# power.net
KiCad netlist of a schematic drawn in Altium Designer
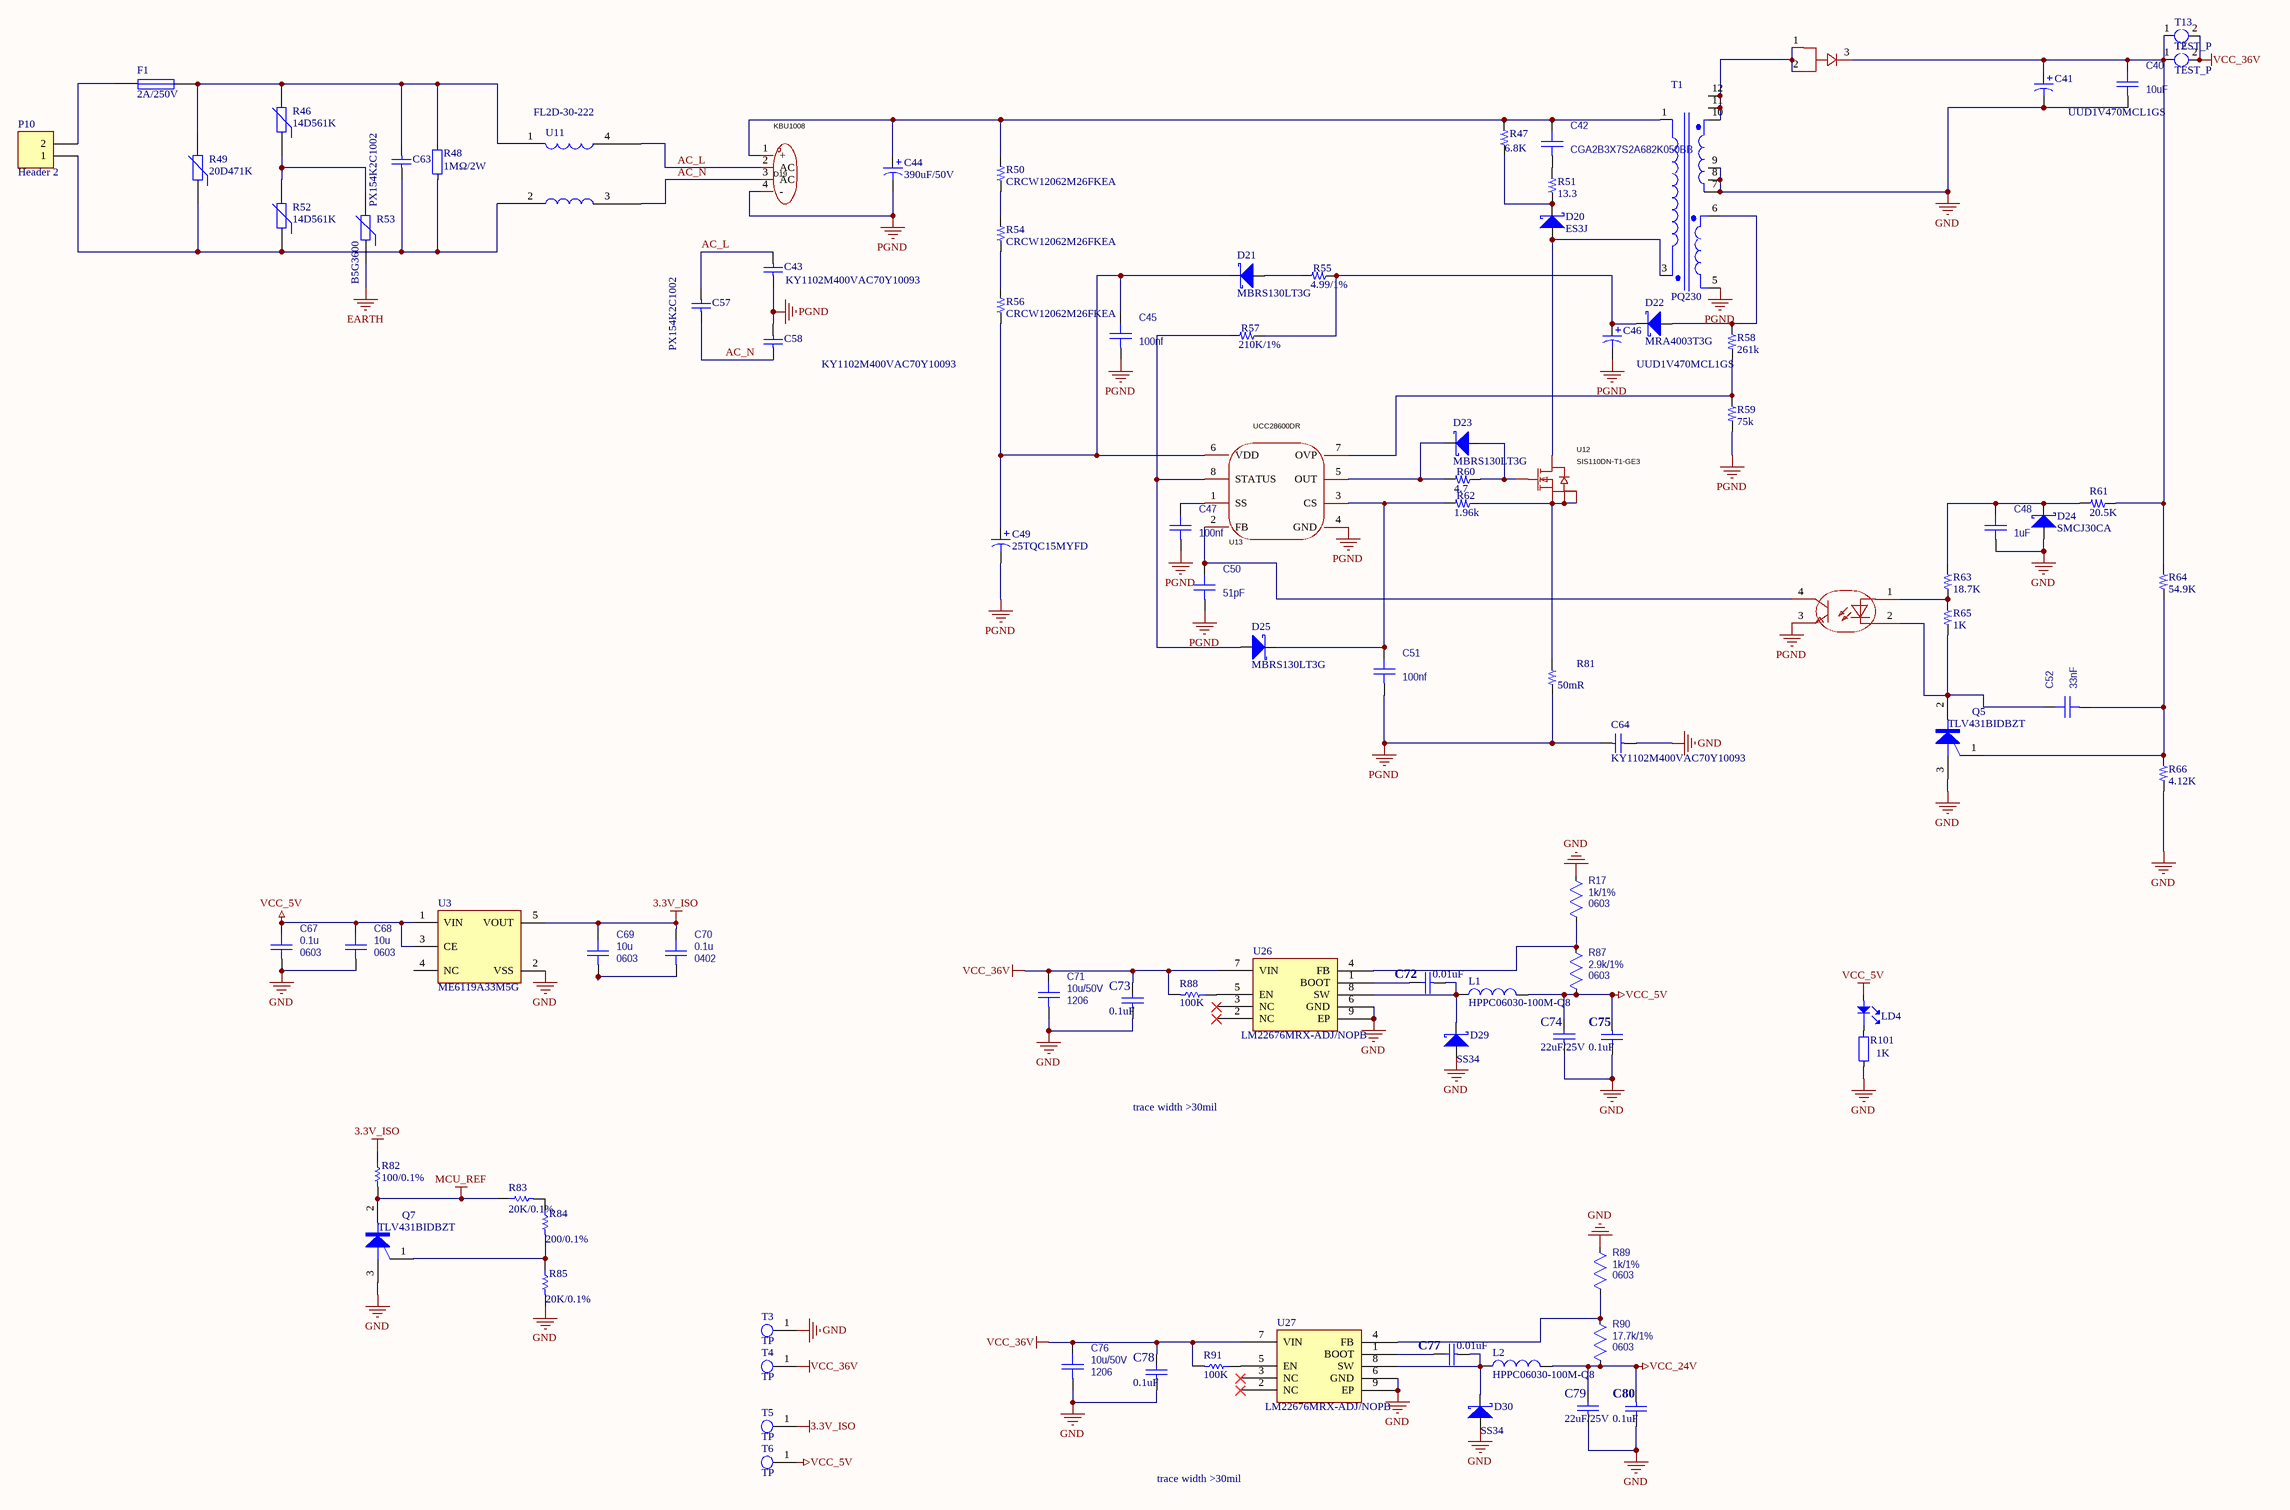
[diagram p0: power.SchDoc]

(export (version "E")
  (design (tool "Eeschema 10.0.6"))
  (components
    (comp (ref "C40")
      (value "Capacitor_0603")
      (footprint "0603c")
      (description "Capacitor, MLCC")
      (fields
        (field (name "MANUFACTURER") "Murata Electronics")
        (field (name "PARTNUMBER") "GRM188R61A106KE69D")
        (field (name "PACKAGE") "10uF")
      )
      (libsource (lib "Karl") (part "Capacitor_0603"))
    )
    (comp (ref "C41")
      (value "UUD1V470MCL1GS")
      (footprint "Φ10×10")
      (description "Polarized Capacitor (Radial)")
      (fields (field (name "PUBLISHER") "Altium Limited"))
      (libsource (lib "Miscellaneous Devices") (part "Cap Pol1"))
    )
    (comp (ref "C42")
      (value "Capacitor_0603")
      (footprint "0402c")
      (description "Capacitor, MLCC")
      (fields
        (field (name "MANUFACTURER") "Murata Electronics")
        (field (name "PARTNUMBER") "GRM188R61A106KE69D")
        (field (name "PACKAGE") "CGA2B3X7S2A682K050BB")
      )
      (libsource (lib "Karl") (part "Capacitor_0603"))
    )
    (comp (ref "C43")
      (value "KY1102M400VAC70Y10093")
      (footprint "CAP-TH_L7.5-W4.5-P10.00-D0.6")
      (description "Capacitor")
      (fields (field (name "PUBLISHER") "Altium Limited"))
      (libsource (lib "Miscellaneous Devices") (part "Cap"))
    )
    (comp (ref "C44")
      (value "390uF/50V")
      (footprint "LGX2H391MELC50")
      (description "Polarized Capacitor (Radial)")
      (fields (field (name "PUBLISHER") "Altium Limited"))
      (libsource (lib "Miscellaneous Devices") (part "Cap Pol1"))
    )
    (comp (ref "C45")
      (value "Capacitor_0603")
      (footprint "0603c")
      (description "Capacitor, MLCC")
      (fields
        (field (name "MANUFACTURER") "Murata Electronics")
        (field (name "PARTNUMBER") "GRM188R61A106KE69D")
        (field (name "PACKAGE") "100nf")
      )
      (libsource (lib "Karl") (part "Capacitor_0603"))
    )
    (comp (ref "C46")
      (value "UUD1V470MCL1GS")
      (footprint "Φ10×10")
      (description "Polarized Capacitor (Radial)")
      (fields (field (name "PUBLISHER") "Altium Limited"))
      (libsource (lib "Miscellaneous Devices") (part "Cap Pol1"))
    )
    (comp (ref "C47")
      (value "Capacitor_0603")
      (footprint "0603c")
      (description "Capacitor, MLCC")
      (fields
        (field (name "MANUFACTURER") "Murata Electronics")
        (field (name "PARTNUMBER") "GRM188R61A106KE69D")
        (field (name "PACKAGE") "100nf")
      )
      (libsource (lib "Karl") (part "Capacitor_0603"))
    )
    (comp (ref "C48")
      (value "Capacitor_0603")
      (footprint "0402c")
      (description "Capacitor, MLCC")
      (fields
        (field (name "MANUFACTURER") "Murata Electronics")
        (field (name "PARTNUMBER") "GRM188R61A106KE69D")
        (field (name "PACKAGE") "1uF")
      )
      (libsource (lib "Karl") (part "Capacitor_0603"))
    )
    (comp (ref "C49")
      (value "25TQC15MYFD")
      (footprint "7343")
      (description "Polarized Capacitor (Radial)")
      (fields (field (name "PUBLISHER") "Altium Limited"))
      (libsource (lib "Miscellaneous Devices") (part "Cap Pol1"))
    )
    (comp (ref "C50")
      (value "Capacitor_0603")
      (footprint "0603c")
      (description "Capacitor, MLCC")
      (fields
        (field (name "MANUFACTURER") "Murata Electronics")
        (field (name "PARTNUMBER") "GRM188R61A106KE69D")
        (field (name "PACKAGE") "51pF")
      )
      (libsource (lib "Karl") (part "Capacitor_0603"))
    )
    (comp (ref "C51")
      (value "Capacitor_0603")
      (footprint "0603c")
      (description "Capacitor, MLCC")
      (fields
        (field (name "MANUFACTURER") "Murata Electronics")
        (field (name "PARTNUMBER") "GRM188R61A106KE69D")
        (field (name "PACKAGE") "100nf")
      )
      (libsource (lib "Karl") (part "Capacitor_0603"))
    )
    (comp (ref "C52")
      (value "Capacitor_0603")
      (footprint "0603c")
      (description "Capacitor, MLCC")
      (fields
        (field (name "MANUFACTURER") "Murata Electronics")
        (field (name "PARTNUMBER") "GRM188R61A106KE69D")
        (field (name "PACKAGE") "33nF")
      )
      (libsource (lib "Karl") (part "Capacitor_0603"))
    )
    (comp (ref "C57")
      (value "PX154K2C1002")
      (footprint "CAP-TH_L13.0-W6.0-P10.00-D0.6")
      (description "Capacitor")
      (fields (field (name "PUBLISHER") "Altium Limited"))
      (libsource (lib "Miscellaneous Devices") (part "Cap"))
    )
    (comp (ref "C58")
      (value "KY1102M400VAC70Y10093")
      (footprint "CAP-TH_L7.5-W4.5-P10.00-D0.6")
      (description "Capacitor")
      (fields (field (name "PUBLISHER") "Altium Limited"))
      (libsource (lib "Miscellaneous Devices") (part "Cap"))
    )
    (comp (ref "C63")
      (value "PX154K2C1002")
      (footprint "CAP-TH_L13.0-W6.0-P10.00-D0.6")
      (description "Capacitor")
      (fields (field (name "PUBLISHER") "Altium Limited"))
      (libsource (lib "Miscellaneous Devices") (part "Cap"))
    )
    (comp (ref "C64")
      (value "KY1102M400VAC70Y10093")
      (footprint "CAP-TH_L7.5-W4.5-P10.00-D0.6")
      (description "Capacitor")
      (fields (field (name "PUBLISHER") "Altium Limited"))
      (libsource (lib "Miscellaneous Devices") (part "Cap"))
    )
    (comp (ref "C67")
      (value "0.1u")
      (footprint "CAPC1608X092N_0603")
      (description "Capacitor, MLCC")
      (fields
        (field (name "MANUFACTURER") "KEMET")
        (field (name "PARTNUMBER") "C0603C104M5RACTU")
        (field (name "PACKAGE") "0603")
      )
      (libsource (lib "Karl") (part "Capacitor_0603"))
    )
    (comp (ref "C68")
      (value "10u")
      (footprint "CAPC1608X092N_0603")
      (description "Capacitor, MLCC")
      (fields
        (field (name "MANUFACTURER") "Murata Electronics")
        (field (name "PARTNUMBER") "GRM188R61A106KE69D")
        (field (name "PACKAGE") "0603")
      )
      (libsource (lib "Karl") (part "Capacitor_0603"))
    )
    (comp (ref "C69")
      (value "10u")
      (footprint "CAPC1608X092N_0603")
      (description "Capacitor, MLCC")
      (fields
        (field (name "MANUFACTURER") "Murata Electronics")
        (field (name "PARTNUMBER") "GRM188R61A106KE69D")
        (field (name "PACKAGE") "0603")
      )
      (libsource (lib "Karl") (part "Capacitor_0603"))
    )
    (comp (ref "C70")
      (value "0.1u")
      (footprint "CAPC1005X056N_0402")
      (description "Capacitor, MLCC")
      (fields
        (field (name "MANUFACTURER") "Murata Electronics")
        (field (name "PARTNUMBER") "GRM155R71C104KA88J")
        (field (name "PACKAGE") "0402")
      )
      (libsource (lib "Karl") (part "Capacitor_0402"))
    )
    (comp (ref "C71")
      (value "10u/50V")
      (footprint "1206C")
      (fields
        (field (name "PARTNUMBER") "C1206C106M3PACTU")
        (field (name "TOLERANCE") "[tol]")
        (field (name "PACKAGE") "1206")
        (field (name "Comment") "Capacitor_1206")
      )
      (libsource (lib "Karl") (part "Capacitor_1206"))
    )
    (comp (ref "C72") (value "0.01uF") (footprint "0603C") (libsource (lib "*") (part "CAP")))
    (comp (ref "C73") (value "0.1uF") (footprint "0603C") (libsource (lib "*") (part "CAP")))
    (comp (ref "C74") (value "22uF/25V") (footprint "1206C") (libsource (lib "*") (part "CAP")))
    (comp (ref "C75") (value "0.1uF") (footprint "0603C") (libsource (lib "*") (part "CAP")))
    (comp (ref "C76")
      (value "10u/50V")
      (footprint "1206C")
      (fields
        (field (name "PARTNUMBER") "C1206C106M3PACTU")
        (field (name "TOLERANCE") "[tol]")
        (field (name "PACKAGE") "1206")
        (field (name "Comment") "Capacitor_1206")
      )
      (libsource (lib "Karl") (part "Capacitor_1206"))
    )
    (comp (ref "C77") (value "0.01uF") (footprint "0603C") (libsource (lib "*") (part "CAP")))
    (comp (ref "C78") (value "0.1uF") (footprint "0603C") (libsource (lib "*") (part "CAP")))
    (comp (ref "C79") (value "22uF/25V") (footprint "1206C") (libsource (lib "*") (part "CAP")))
    (comp (ref "C80") (value "0.1uF") (footprint "0603C") (libsource (lib "*") (part "CAP")))
    (comp (ref "D18")
      (value "SVT12100VB_R2_00001")
      (footprint "TO-277B_3P-L6.1-W4.3-LS7.0-BR")
      (fields (field (name "MANUFACTURER") "PANJIT(强茂)"))
      (libsource (lib "altium-import") (part "root_2_SVT12100VB_R2_00001_"))
    )
    (comp (ref "D19")
      (value "KBU1008")
      (footprint "KBU_4P-L23.2-W6.8-P5.10")
      (fields (field (name "MANUFACTURER") "YANGJIE(扬杰)"))
      (libsource (lib "altium-import") (part "root_0_KBU1008_"))
    )
    (comp (ref "D20")
      (value "ES3J")
      (footprint "SMC")
      (description "Schottky Diode")
      (libsource (lib "*") (part "DIODE S"))
    )
    (comp (ref "D21")
      (value "MBRS130LT3G")
      (footprint "SMB")
      (description "Schottky Diode")
      (libsource (lib "*") (part "DIODE S"))
    )
    (comp (ref "D22")
      (value "MRA4003T3G")
      (footprint "SMA")
      (description "Schottky Diode")
      (libsource (lib "*") (part "DIODE S"))
    )
    (comp (ref "D23")
      (value "MBRS130LT3G")
      (footprint "SMB")
      (description "Schottky Diode")
      (libsource (lib "*") (part "DIODE S"))
    )
    (comp (ref "D24")
      (value "SMCJ30CA")
      (footprint "SMC")
      (description "Schottky Diode")
      (libsource (lib "*") (part "DIODE S"))
    )
    (comp (ref "D25")
      (value "MBRS130LT3G")
      (footprint "SMB")
      (description "Schottky Diode")
      (libsource (lib "*") (part "DIODE S"))
    )
    (comp (ref "D29") (value "SS34") (footprint "SMA") (libsource (lib "*") (part "DIODE S")))
    (comp (ref "D30") (value "SS34") (footprint "SMA") (libsource (lib "*") (part "DIODE S")))
    (comp (ref "F1")
      (value "2A/250V")
      (footprint "可视开关电源保险丝座")
      (description "Fuse")
      (fields (field (name "PUBLISHER") "Altium Limited"))
      (libsource (lib "Miscellaneous Devices") (part "Fuse 1"))
    )
    (comp (ref "L1")
      (value "HPPC06030-100M-Q8")
      (footprint "IND-SMD-L7.3-W6")
      (fields (field (name "PARTNUMBER") "1276AS-H-100M=P2"))
      (libsource (lib "Bogen") (part "1276AS-H-100M=P2"))
    )
    (comp (ref "L2")
      (value "HPPC06030-100M-Q8")
      (footprint "IND-SMD-L7.3-W6")
      (fields (field (name "PARTNUMBER") "1276AS-H-100M=P2"))
      (libsource (lib "Bogen") (part "1276AS-H-100M=P2"))
    )
    (comp (ref "LD4")
      (value "LED_Green_19-217")
      (footprint "0603led")
      (libsource (lib "RC_M_D_00") (part "LED_Green_19-217"))
    )
    (comp (ref "P10")
      (value "Header 2")
      (footprint "HDR1X2")
      (description "Header, 2-Pin")
      (fields (field (name "PUBLISHER") "Altium Limited"))
      (libsource (lib "Miscellaneous Connectors") (part "Header 2"))
    )
    (comp (ref "Q5")
      (value "TLV431BIDBZT")
      (footprint "SOT23-3")
      (description "Programmable Unijunction Transistor")
      (fields (field (name "PUBLISHER") "Altium Limited"))
      (libsource (lib "Miscellaneous Devices") (part "PUT"))
    )
    (comp (ref "Q7")
      (value "TLV431BIDBZT")
      (footprint "SOT23-3")
      (description "Programmable Unijunction Transistor")
      (fields (field (name "PUBLISHER") "Altium Limited"))
      (libsource (lib "Miscellaneous Devices") (part "PUT"))
    )
    (comp (ref "R17")
      (value "1k/1%")
      (footprint "0603R")
      (fields
        (field (name "PARTNUMBER") "RC0603FR-1075KL")
        (field (name "TOLERANCE") "tol")
        (field (name "PACKAGE") "0603")
        (field (name "Comment") "Resistor_0603")
      )
      (libsource (lib "Karl") (part "Resistor_0603"))
    )
    (comp (ref "R46")
      (value "14D561K")
      (footprint "14D561K")
      (description "Varistor (Voltage-Sensitive Resistor)")
      (fields (field (name "PUBLISHER") "Altium Limited"))
      (libsource (lib "Miscellaneous Devices") (part "Res Varistor"))
    )
    (comp (ref "R47")
      (value "6.8K")
      (footprint "0603R")
      (description "R")
      (libsource (lib "JRJ_1") (part "R"))
    )
    (comp (ref "R48") (value "1MΩ/2W") (footprint "5x15.5") (libsource (lib "RC_M_D_00") (part "RES0603")))
    (comp (ref "R49")
      (value "20D471K")
      (footprint "20D471K")
      (description "Varistor (Voltage-Sensitive Resistor)")
      (fields (field (name "PUBLISHER") "Altium Limited"))
      (libsource (lib "Miscellaneous Devices") (part "Res Varistor"))
    )
    (comp (ref "R50")
      (value "CRCW12062M26FKEA")
      (footprint "1206R")
      (description "R")
      (libsource (lib "JRJ_1") (part "R"))
    )
    (comp (ref "R51")
      (value "13.3")
      (footprint "0603R")
      (description "R")
      (libsource (lib "JRJ_1") (part "R"))
    )
    (comp (ref "R52")
      (value "14D561K")
      (footprint "14D561K")
      (description "Varistor (Voltage-Sensitive Resistor)")
      (fields (field (name "PUBLISHER") "Altium Limited"))
      (libsource (lib "Miscellaneous Devices") (part "Res Varistor"))
    )
    (comp (ref "R53")
      (value "B5G3600")
      (footprint "B5G3600")
      (description "Varistor (Voltage-Sensitive Resistor)")
      (fields (field (name "PUBLISHER") "Altium Limited"))
      (libsource (lib "Miscellaneous Devices") (part "Res Varistor"))
    )
    (comp (ref "R54")
      (value "CRCW12062M26FKEA")
      (footprint "1206R")
      (description "R")
      (libsource (lib "JRJ_1") (part "R"))
    )
    (comp (ref "R55")
      (value "4.99/1%")
      (footprint "0603R")
      (description "R")
      (libsource (lib "JRJ_1") (part "R"))
    )
    (comp (ref "R56")
      (value "CRCW12062M26FKEA")
      (footprint "1206R")
      (description "R")
      (libsource (lib "JRJ_1") (part "R"))
    )
    (comp (ref "R57")
      (value "210K/1%")
      (footprint "0603R")
      (description "R")
      (libsource (lib "JRJ_1") (part "R"))
    )
    (comp (ref "R58")
      (value "261k")
      (footprint "0603R")
      (description "R")
      (libsource (lib "JRJ_1") (part "R"))
    )
    (comp (ref "R59")
      (value "75k")
      (footprint "0603R")
      (description "R")
      (libsource (lib "JRJ_1") (part "R"))
    )
    (comp (ref "R60")
      (value "4.7")
      (footprint "0603R")
      (description "R")
      (libsource (lib "JRJ_1") (part "R"))
    )
    (comp (ref "R61")
      (value "20.5K")
      (footprint "0603R")
      (description "R")
      (libsource (lib "JRJ_1") (part "R"))
    )
    (comp (ref "R62")
      (value "1.96k")
      (footprint "0603R")
      (description "R")
      (libsource (lib "JRJ_1") (part "R"))
    )
    (comp (ref "R63")
      (value "18.7K")
      (footprint "0603R")
      (description "R")
      (libsource (lib "JRJ_1") (part "R"))
    )
    (comp (ref "R64")
      (value "54.9K")
      (footprint "0603R")
      (description "R")
      (libsource (lib "JRJ_1") (part "R"))
    )
    (comp (ref "R65") (value "1K") (footprint "0603R") (description "R") (libsource (lib "JRJ_1") (part "R")))
    (comp (ref "R66")
      (value "4.12K")
      (footprint "0603R")
      (description "R")
      (libsource (lib "JRJ_1") (part "R"))
    )
    (comp (ref "R81")
      (value "50mR")
      (footprint "2512R")
      (description "R")
      (libsource (lib "JRJ_1") (part "R"))
    )
    (comp (ref "R82")
      (value "100/0.1%")
      (footprint "0603R")
      (description "Resistor")
      (fields (field (name "PUBLISHER") "Altium Limited"))
      (libsource (lib "Miscellaneous Devices") (part "Res1"))
    )
    (comp (ref "R83")
      (value "20K/0.1%")
      (footprint "0603R")
      (description "Resistor")
      (fields (field (name "Comment") "1K/0.1%") (field (name "PUBLISHER") "Altium Limited"))
      (libsource (lib "Miscellaneous Devices") (part "Res1"))
    )
    (comp (ref "R84")
      (value "200/0.1%")
      (footprint "0603R")
      (description "Resistor")
      (fields (field (name "Comment") "1K/0.1%") (field (name "PUBLISHER") "Altium Limited"))
      (libsource (lib "Miscellaneous Devices") (part "Res1"))
    )
    (comp (ref "R85")
      (value "20K/0.1%")
      (footprint "0603R")
      (description "Resistor")
      (fields (field (name "Comment") "1K/0.1%") (field (name "PUBLISHER") "Altium Limited"))
      (libsource (lib "Miscellaneous Devices") (part "Res1"))
    )
    (comp (ref "R87")
      (value "2.9k/1%")
      (footprint "0603R")
      (fields
        (field (name "PARTNUMBER") "RC0603FR-1075KL")
        (field (name "TOLERANCE") "tol")
        (field (name "PACKAGE") "0603")
        (field (name "Comment") "Resistor_0603")
      )
      (libsource (lib "Karl") (part "Resistor_0603"))
    )
    (comp (ref "R88")
      (value "100K")
      (footprint "0603R")
      (fields (field (name "PUBLISHER") "Altium Limited"))
      (libsource (lib "Miscellaneous Devices") (part "Res1"))
    )
    (comp (ref "R89")
      (value "1k/1%")
      (footprint "0603R")
      (fields
        (field (name "PARTNUMBER") "RC0603FR-1075KL")
        (field (name "TOLERANCE") "tol")
        (field (name "PACKAGE") "0603")
        (field (name "Comment") "Resistor_0603")
      )
      (libsource (lib "Karl") (part "Resistor_0603"))
    )
    (comp (ref "R90")
      (value "17.7k/1%")
      (footprint "0603R")
      (fields
        (field (name "PARTNUMBER") "RC0603FR-1075KL")
        (field (name "TOLERANCE") "tol")
        (field (name "PACKAGE") "0603")
        (field (name "Comment") "Resistor_0603")
      )
      (libsource (lib "Karl") (part "Resistor_0603"))
    )
    (comp (ref "R91")
      (value "100K")
      (footprint "0603R")
      (fields (field (name "PUBLISHER") "Altium Limited"))
      (libsource (lib "Miscellaneous Devices") (part "Res1"))
    )
    (comp (ref "R101") (value "1K") (footprint "0603r") (libsource (lib "RC_M_D_00") (part "RES0603")))
    (comp (ref "T1") (value "PQ230") (footprint "pq3230") (libsource (lib "Schlib_20110825") (part "PQ230")))
    (comp (ref "T2")
      (value "TEST_P")
      (footprint "TEST_P")
      (libsource (lib "Schlib_20110825") (part "TEST_P"))
    )
    (comp (ref "T3") (value "TP") (footprint "TPD") (libsource (lib "Schlib_20110825") (part "TP")))
    (comp (ref "T4") (value "TP") (footprint "TPD") (libsource (lib "Schlib_20110825") (part "TP")))
    (comp (ref "T5") (value "TP") (footprint "TPD") (libsource (lib "Schlib_20110825") (part "TP")))
    (comp (ref "T6") (value "TP") (footprint "TPD") (libsource (lib "Schlib_20110825") (part "TP")))
    (comp (ref "T13")
      (value "TEST_P")
      (footprint "TEST_P")
      (libsource (lib "Schlib_20110825") (part "TEST_P"))
    )
    (comp (ref "U3")
      (value "ME6119A33M5G")
      (footprint "MCRN-SOT23-5_V")
      (libsource (lib "Bogen") (part "ME6119C50M5G"))
    )
    (comp (ref "U11")
      (value "FL2D-30-222")
      (footprint "TY-100P")
      (description "PCB mounting filters")
      (libsource (lib "power") (part "TY-100P"))
    )
    (comp (ref "U12")
      (value "SIS110DN-T1-GE3")
      (footprint "DFN-8_L3.3-W3.3-P0.65-BL-2")
      (fields (field (name "MANUFACTURER") "VISHAY(威世)"))
      (libsource (lib "altium-import") (part "root_0_SIS110DN-T1-GE3_"))
    )
    (comp (ref "U13")
      (value "UCC28600DR")
      (footprint "so-8")
      (fields (field (name "MANUFACTURER") "TI(德州仪器)"))
      (libsource (lib "UCC28600DR1_UCC28600DR") (part "UCC28600DR"))
    )
    (comp (ref "U14")
      (value "TCMT1107")
      (footprint "sop4")
      (fields (field (name "MANUFACTURER") "VISHAY(威世)"))
      (libsource (lib "altium-import") (part "root_0_mirrored_TCMT1107_"))
    )
    (comp (ref "U26")
      (value "LM22676MRX-ADJ/NOPB")
      (footprint "SOP127P600X168_HS-8N")
      (libsource (lib "Schlib1") (part "LM22676MR-5.0"))
    )
    (comp (ref "U27")
      (value "LM22676MRX-ADJ/NOPB")
      (footprint "SOP127P600X168_HS-8N")
      (libsource (lib "Schlib1") (part "LM22676MR-5.0"))
    )
  )
  (nets
    (net (code "1") (name "/AC_L") (class "Default")
      (node (ref "C43") (pin "2") (pinfunction "2_2") (pintype "passive"))
      (node (ref "C57") (pin "2") (pinfunction "2_2") (pintype "passive"))
      (node (ref "D19") (pin "2") (pinfunction "AC_2") (pintype "passive"))
      (node (ref "U11") (pin "4") (pinfunction "L_4") (pintype "passive"))
    )
    (net (code "2") (name "/AC_N") (class "Default")
      (node (ref "C57") (pin "1") (pinfunction "1_1") (pintype "passive"))
      (node (ref "C58") (pin "1") (pinfunction "1_1") (pintype "passive"))
      (node (ref "D19") (pin "3") (pinfunction "AC_3") (pintype "passive"))
      (node (ref "U11") (pin "3") (pintype "passive"))
    )
    (net (code "3") (name "3.3V_ISO") (class "Default")
      (node (ref "C69") (pin "1") (pinfunction "1_1") (pintype "passive"))
      (node (ref "C70") (pin "1") (pinfunction "1_1") (pintype "passive"))
      (node (ref "R82") (pin "1") (pinfunction "1_1") (pintype "passive"))
      (node (ref "T5") (pin "1") (pintype "passive"))
      (node (ref "U3") (pin "5") (pinfunction "VOUT_5") (pintype "passive"))
    )
    (net (code "4") (name "EARTH") (class "Default")
      (node (ref "R53") (pin "1") (pinfunction "1_1") (pintype "passive"))
    )
    (net (code "5") (name "GND") (class "Default")
      (node (ref "C40") (pin "2") (pinfunction "2_2") (pintype "passive"))
      (node (ref "C41") (pin "2") (pinfunction "2_2") (pintype "passive"))
      (node (ref "C48") (pin "2") (pinfunction "2_2") (pintype "passive"))
      (node (ref "C64") (pin "1") (pinfunction "1_1") (pintype "passive"))
      (node (ref "C67") (pin "2") (pinfunction "2_2") (pintype "passive"))
      (node (ref "C68") (pin "2") (pinfunction "2_2") (pintype "passive"))
      (node (ref "C71") (pin "2") (pinfunction "2_2") (pintype "passive"))
      (node (ref "C73") (pin "1") (pinfunction "1_1") (pintype "passive"))
      (node (ref "C74") (pin "1") (pinfunction "1_1") (pintype "passive"))
      (node (ref "C75") (pin "2") (pinfunction "2_2") (pintype "passive"))
      (node (ref "C76") (pin "2") (pinfunction "2_2") (pintype "passive"))
      (node (ref "C78") (pin "1") (pinfunction "1_1") (pintype "passive"))
      (node (ref "C79") (pin "1") (pinfunction "1_1") (pintype "passive"))
      (node (ref "C80") (pin "2") (pinfunction "2_2") (pintype "passive"))
      (node (ref "D24") (pin "1") (pinfunction "A_1") (pintype "passive"))
      (node (ref "D29") (pin "1") (pinfunction "A_1") (pintype "passive"))
      (node (ref "D30") (pin "1") (pinfunction "A_1") (pintype "passive"))
      (node (ref "Q5") (pin "3") (pinfunction "A_3") (pintype "passive"))
      (node (ref "Q7") (pin "3") (pinfunction "A_3") (pintype "passive"))
      (node (ref "R101") (pin "2") (pinfunction "2_2") (pintype "passive"))
      (node (ref "R17") (pin "2") (pinfunction "2_2") (pintype "passive"))
      (node (ref "R66") (pin "2") (pintype "passive"))
      (node (ref "R85") (pin "2") (pinfunction "2_2") (pintype "passive"))
      (node (ref "R89") (pin "2") (pinfunction "2_2") (pintype "passive"))
      (node (ref "T1") (pin "7") (pinfunction "Pri-_7") (pintype "passive"))
      (node (ref "T1") (pin "8") (pinfunction "Pri-_8") (pintype "passive"))
      (node (ref "T1") (pin "9") (pinfunction "Pri-_9") (pintype "passive"))
      (node (ref "T3") (pin "1") (pintype "passive"))
      (node (ref "U26") (pin "6") (pinfunction "GND_6") (pintype "passive"))
      (node (ref "U26") (pin "9") (pinfunction "EP_9") (pintype "passive"))
      (node (ref "U27") (pin "6") (pinfunction "GND_6") (pintype "passive"))
      (node (ref "U27") (pin "9") (pinfunction "EP_9") (pintype "passive"))
      (node (ref "U3") (pin "2") (pinfunction "VSS_2") (pintype "passive"))
    )
    (net (code "6") (name "MCU_REF") (class "Default")
      (node (ref "Q7") (pin "2") (pinfunction "K_2") (pintype "passive"))
      (node (ref "R82") (pin "2") (pinfunction "2_2") (pintype "passive"))
      (node (ref "R83") (pin "1") (pinfunction "1_1") (pintype "passive"))
    )
    (net (code "7") (name "Net-(C40-Pad1)") (class "Default")
      (node (ref "C40") (pin "1") (pinfunction "1_1") (pintype "passive"))
      (node (ref "C41") (pin "1") (pinfunction "1_1") (pintype "passive"))
      (node (ref "D18") (pin "3") (pinfunction "3_3") (pintype "passive"))
      (node (ref "R61") (pin "1") (pintype "passive"))
      (node (ref "R64") (pin "1") (pintype "passive"))
      (node (ref "T13") (pin "1") (pinfunction "1_1") (pintype "passive"))
      (node (ref "T2") (pin "1") (pinfunction "1_1") (pintype "passive"))
    )
    (net (code "8") (name "Net-(C42-Pad2)") (class "Default")
      (node (ref "C42") (pin "2") (pinfunction "2_2") (pintype "passive"))
      (node (ref "R51") (pin "2") (pintype "passive"))
    )
    (net (code "9") (name "Net-(C63-Pad1)") (class "Default")
      (node (ref "C63") (pin "1") (pinfunction "1_1") (pintype "passive"))
      (node (ref "P10") (pin "1") (pinfunction "1_1") (pintype "passive"))
      (node (ref "R48") (pin "2") (pinfunction "2_2") (pintype "passive"))
      (node (ref "R49") (pin "1") (pinfunction "1_1") (pintype "passive"))
      (node (ref "R52") (pin "1") (pinfunction "1_1") (pintype "passive"))
      (node (ref "U11") (pin "2") (pinfunction "L_2") (pintype "passive"))
    )
    (net (code "10") (name "Net-(C63-Pad2)") (class "Default")
      (node (ref "C63") (pin "2") (pinfunction "2_2") (pintype "passive"))
      (node (ref "F1") (pin "2") (pinfunction "2_2") (pintype "passive"))
      (node (ref "R46") (pin "2") (pinfunction "2_2") (pintype "passive"))
      (node (ref "R48") (pin "1") (pinfunction "1_1") (pintype "passive"))
      (node (ref "R49") (pin "2") (pinfunction "2_2") (pintype "passive"))
      (node (ref "U11") (pin "1") (pinfunction "L_1") (pintype "passive"))
    )
    (net (code "11") (name "Net-(C69-Pad2)") (class "Default")
      (node (ref "C69") (pin "2") (pinfunction "2_2") (pintype "passive"))
      (node (ref "C70") (pin "2") (pinfunction "2_2") (pintype "passive"))
    )
    (net (code "12") (name "Net-(D18-Pad1)") (class "Default")
      (node (ref "D18") (pin "1") (pinfunction "1_1") (pintype "passive"))
      (node (ref "D18") (pin "2") (pinfunction "2_2") (pintype "passive"))
      (node (ref "T1") (pin "10") (pinfunction "Pri+_10") (pintype "passive"))
      (node (ref "T1") (pin "11") (pinfunction "Pri+_11") (pintype "passive"))
      (node (ref "T1") (pin "12") (pinfunction "Pri+_12") (pintype "passive"))
    )
    (net (code "13") (name "Net-(D19-+)") (class "Default")
      (node (ref "C42") (pin "1") (pinfunction "1_1") (pintype "passive"))
      (node (ref "C44") (pin "1") (pinfunction "1_1") (pintype "passive"))
      (node (ref "D19") (pin "1") (pinfunction "+_1") (pintype "passive"))
      (node (ref "R47") (pin "2") (pintype "passive"))
      (node (ref "R50") (pin "2") (pintype "passive"))
      (node (ref "T1") (pin "1") (pinfunction "Pri+_1") (pintype "passive"))
    )
    (net (code "14") (name "Net-(D20-A)") (class "Default")
      (node (ref "D20") (pin "1") (pinfunction "A_1") (pintype "passive"))
      (node (ref "T1") (pin "3") (pinfunction "Pri-_3") (pintype "passive"))
      (node (ref "U12") (pin "5") (pinfunction "D_5") (pintype "passive"))
    )
    (net (code "15") (name "Net-(D20-K)") (class "Default")
      (node (ref "D20") (pin "2") (pinfunction "K_2") (pintype "passive"))
      (node (ref "R47") (pin "1") (pintype "passive"))
      (node (ref "R51") (pin "1") (pintype "passive"))
    )
    (net (code "16") (name "Net-(D21-A)") (class "Default")
      (node (ref "D21") (pin "1") (pinfunction "A_1") (pintype "passive"))
      (node (ref "R55") (pin "2") (pintype "passive"))
    )
    (net (code "17") (name "Net-(D21-K)") (class "Default")
      (node (ref "C45") (pin "1") (pinfunction "1_1") (pintype "passive"))
      (node (ref "C49") (pin "1") (pinfunction "1_1") (pintype "passive"))
      (node (ref "D21") (pin "2") (pinfunction "K_2") (pintype "passive"))
      (node (ref "R56") (pin "1") (pintype "passive"))
      (node (ref "U13") (pin "6") (pinfunction "VDD_6") (pintype "passive"))
    )
    (net (code "18") (name "Net-(D22-A)") (class "Default")
      (node (ref "D22") (pin "1") (pinfunction "A_1") (pintype "passive"))
      (node (ref "R58") (pin "1") (pintype "passive"))
      (node (ref "T1") (pin "6") (pinfunction "Pri-_6") (pintype "passive"))
    )
    (net (code "19") (name "Net-(D22-K)") (class "Default")
      (node (ref "C46") (pin "1") (pinfunction "1_1") (pintype "passive"))
      (node (ref "D22") (pin "2") (pinfunction "K_2") (pintype "passive"))
      (node (ref "R55") (pin "1") (pintype "passive"))
      (node (ref "R57") (pin "1") (pintype "passive"))
    )
    (net (code "20") (name "Net-(D23-A)") (class "Default")
      (node (ref "D23") (pin "1") (pinfunction "A_1") (pintype "passive"))
      (node (ref "R60") (pin "1") (pintype "passive"))
      (node (ref "U12") (pin "4") (pinfunction "G_4") (pintype "passive"))
    )
    (net (code "21") (name "Net-(D23-K)") (class "Default")
      (node (ref "D23") (pin "2") (pinfunction "K_2") (pintype "passive"))
      (node (ref "R60") (pin "2") (pintype "passive"))
      (node (ref "U13") (pin "5") (pinfunction "OUT_5") (pintype "passive"))
    )
    (net (code "22") (name "Net-(D24-K)") (class "Default")
      (node (ref "C48") (pin "1") (pinfunction "1_1") (pintype "passive"))
      (node (ref "D24") (pin "2") (pinfunction "K_2") (pintype "passive"))
      (node (ref "R61") (pin "2") (pintype "passive"))
      (node (ref "R63") (pin "1") (pintype "passive"))
    )
    (net (code "23") (name "Net-(D25-A)") (class "Default")
      (node (ref "D25") (pin "1") (pinfunction "A_1") (pintype "passive"))
      (node (ref "R57") (pin "2") (pintype "passive"))
      (node (ref "U13") (pin "8") (pinfunction "STATUS_8") (pintype "passive"))
    )
    (net (code "24") (name "Net-(D25-K)") (class "Default")
      (node (ref "C51") (pin "1") (pinfunction "1_1") (pintype "passive"))
      (node (ref "D25") (pin "2") (pinfunction "K_2") (pintype "passive"))
      (node (ref "R62") (pin "2") (pintype "passive"))
      (node (ref "U13") (pin "3") (pinfunction "CS_3") (pintype "passive"))
    )
    (net (code "25") (name "Net-(D29-K)") (class "Default")
      (node (ref "C72") (pin "1") (pinfunction "1_1") (pintype "passive"))
      (node (ref "D29") (pin "2") (pinfunction "K_2") (pintype "passive"))
      (node (ref "L1") (pin "1") (pinfunction "1_1") (pintype "passive"))
      (node (ref "U26") (pin "8") (pinfunction "SW_8") (pintype "passive"))
    )
    (net (code "26") (name "Net-(D30-K)") (class "Default")
      (node (ref "C77") (pin "1") (pinfunction "1_1") (pintype "passive"))
      (node (ref "D30") (pin "2") (pinfunction "K_2") (pintype "passive"))
      (node (ref "L2") (pin "1") (pinfunction "1_1") (pintype "passive"))
      (node (ref "U27") (pin "8") (pinfunction "SW_8") (pintype "passive"))
    )
    (net (code "27") (name "Net-(F1-Pad1)") (class "Default")
      (node (ref "F1") (pin "1") (pinfunction "1_1") (pintype "passive"))
      (node (ref "P10") (pin "2") (pinfunction "2_2") (pintype "passive"))
    )
    (net (code "28") (name "Net-(LD4-Pad2)") (class "Default")
      (node (ref "LD4") (pin "2") (pinfunction "2_2") (pintype "passive"))
      (node (ref "R101") (pin "1") (pinfunction "1_1") (pintype "passive"))
    )
    (net (code "29") (name "Net-(Q5-G)") (class "Default")
      (node (ref "C52") (pin "2") (pinfunction "2_2") (pintype "passive"))
      (node (ref "Q5") (pin "1") (pinfunction "G_1") (pintype "passive"))
      (node (ref "R64") (pin "2") (pintype "passive"))
      (node (ref "R66") (pin "1") (pintype "passive"))
    )
    (net (code "30") (name "Net-(Q5-K)") (class "Default")
      (node (ref "C52") (pin "1") (pinfunction "1_1") (pintype "passive"))
      (node (ref "Q5") (pin "2") (pinfunction "K_2") (pintype "passive"))
      (node (ref "R65") (pin "2") (pintype "passive"))
      (node (ref "U14") (pin "2") (pinfunction "CAT_2") (pintype "passive"))
    )
    (net (code "31") (name "Net-(Q7-G)") (class "Default")
      (node (ref "Q7") (pin "1") (pinfunction "G_1") (pintype "passive"))
      (node (ref "R84") (pin "2") (pinfunction "2_2") (pintype "passive"))
      (node (ref "R85") (pin "1") (pinfunction "1_1") (pintype "passive"))
    )
    (net (code "32") (name "Net-(R46-Pad1)") (class "Default")
      (node (ref "R46") (pin "1") (pinfunction "1_1") (pintype "passive"))
      (node (ref "R52") (pin "2") (pinfunction "2_2") (pintype "passive"))
      (node (ref "R53") (pin "2") (pinfunction "2_2") (pintype "passive"))
    )
    (net (code "33") (name "Net-(R50-Pad1)") (class "Default")
      (node (ref "R50") (pin "1") (pintype "passive"))
      (node (ref "R54") (pin "2") (pintype "passive"))
    )
    (net (code "34") (name "Net-(R54-Pad1)") (class "Default")
      (node (ref "R54") (pin "1") (pintype "passive"))
      (node (ref "R56") (pin "2") (pintype "passive"))
    )
    (net (code "35") (name "Net-(R62-Pad1)") (class "Default")
      (node (ref "R62") (pin "1") (pintype "passive"))
      (node (ref "R81") (pin "1") (pintype "passive"))
      (node (ref "U12") (pin "1") (pinfunction "S_1") (pintype "passive"))
      (node (ref "U12") (pin "2") (pinfunction "S_2") (pintype "passive"))
      (node (ref "U12") (pin "3") (pinfunction "S_3") (pintype "passive"))
    )
    (net (code "36") (name "Net-(R83-Pad2)") (class "Default")
      (node (ref "R83") (pin "2") (pinfunction "2_2") (pintype "passive"))
      (node (ref "R84") (pin "1") (pinfunction "1_1") (pintype "passive"))
    )
    (net (code "37") (name "Net-(U13-FB)") (class "Default")
      (node (ref "C50") (pin "1") (pinfunction "1_1") (pintype "passive"))
      (node (ref "U13") (pin "2") (pinfunction "FB_2") (pintype "passive"))
      (node (ref "U14") (pin "4") (pinfunction "COL_4") (pintype "passive"))
    )
    (net (code "38") (name "Net-(U13-OVP)") (class "Default")
      (node (ref "R58") (pin "2") (pintype "passive"))
      (node (ref "R59") (pin "1") (pintype "passive"))
      (node (ref "U13") (pin "7") (pinfunction "OVP_7") (pintype "passive"))
    )
    (net (code "39") (name "Net-(U13-SS)") (class "Default")
      (node (ref "C47") (pin "1") (pinfunction "1_1") (pintype "passive"))
      (node (ref "U13") (pin "1") (pinfunction "SS_1") (pintype "passive"))
    )
    (net (code "40") (name "Net-(U14-AN)") (class "Default")
      (node (ref "R63") (pin "2") (pintype "passive"))
      (node (ref "R65") (pin "1") (pintype "passive"))
      (node (ref "U14") (pin "1") (pinfunction "AN_1") (pintype "passive"))
    )
    (net (code "41") (name "Net-(U26-BOOT)") (class "Default")
      (node (ref "C72") (pin "2") (pinfunction "2_2") (pintype "passive"))
      (node (ref "U26") (pin "1") (pinfunction "BOOT_1") (pintype "passive"))
    )
    (net (code "42") (name "Net-(U26-EN)") (class "Default")
      (node (ref "R88") (pin "1") (pinfunction "1_1") (pintype "passive"))
      (node (ref "U26") (pin "5") (pinfunction "EN_5") (pintype "passive"))
    )
    (net (code "43") (name "Net-(U26-FB)") (class "Default")
      (node (ref "R17") (pin "1") (pinfunction "1_1") (pintype "passive"))
      (node (ref "R87") (pin "2") (pinfunction "2_2") (pintype "passive"))
      (node (ref "U26") (pin "4") (pinfunction "FB_4") (pintype "passive"))
    )
    (net (code "44") (name "Net-(U27-BOOT)") (class "Default")
      (node (ref "C77") (pin "2") (pinfunction "2_2") (pintype "passive"))
      (node (ref "U27") (pin "1") (pinfunction "BOOT_1") (pintype "passive"))
    )
    (net (code "45") (name "Net-(U27-EN)") (class "Default")
      (node (ref "R91") (pin "1") (pinfunction "1_1") (pintype "passive"))
      (node (ref "U27") (pin "5") (pinfunction "EN_5") (pintype "passive"))
    )
    (net (code "46") (name "Net-(U27-FB)") (class "Default")
      (node (ref "R89") (pin "1") (pinfunction "1_1") (pintype "passive"))
      (node (ref "R90") (pin "2") (pinfunction "2_2") (pintype "passive"))
      (node (ref "U27") (pin "4") (pinfunction "FB_4") (pintype "passive"))
    )
    (net (code "47") (name "PGND") (class "Default")
      (node (ref "C43") (pin "1") (pinfunction "1_1") (pintype "passive"))
      (node (ref "C44") (pin "2") (pinfunction "2_2") (pintype "passive"))
      (node (ref "C45") (pin "2") (pinfunction "2_2") (pintype "passive"))
      (node (ref "C46") (pin "2") (pinfunction "2_2") (pintype "passive"))
      (node (ref "C47") (pin "2") (pinfunction "2_2") (pintype "passive"))
      (node (ref "C49") (pin "2") (pinfunction "2_2") (pintype "passive"))
      (node (ref "C50") (pin "2") (pinfunction "2_2") (pintype "passive"))
      (node (ref "C51") (pin "2") (pinfunction "2_2") (pintype "passive"))
      (node (ref "C58") (pin "2") (pinfunction "2_2") (pintype "passive"))
      (node (ref "C64") (pin "2") (pinfunction "2_2") (pintype "passive"))
      (node (ref "D19") (pin "4") (pinfunction "-_4") (pintype "passive"))
      (node (ref "R59") (pin "2") (pintype "passive"))
      (node (ref "R81") (pin "2") (pintype "passive"))
      (node (ref "T1") (pin "5") (pinfunction "Pri-_5") (pintype "passive"))
      (node (ref "U13") (pin "4") (pinfunction "GND_4") (pintype "passive"))
      (node (ref "U14") (pin "3") (pinfunction "EM_3") (pintype "passive"))
    )
    (net (code "48") (name "VCC_5V") (class "Default")
      (node (ref "C67") (pin "1") (pinfunction "1_1") (pintype "passive"))
      (node (ref "C68") (pin "1") (pinfunction "1_1") (pintype "passive"))
      (node (ref "C74") (pin "2") (pinfunction "2_2") (pintype "passive"))
      (node (ref "C75") (pin "1") (pinfunction "1_1") (pintype "passive"))
      (node (ref "L1") (pin "2") (pinfunction "2_2") (pintype "passive"))
      (node (ref "LD4") (pin "1") (pinfunction "1_1") (pintype "passive"))
      (node (ref "R87") (pin "1") (pinfunction "1_1") (pintype "passive"))
      (node (ref "T6") (pin "1") (pintype "passive"))
      (node (ref "U3") (pin "1") (pinfunction "VIN_1") (pintype "passive"))
      (node (ref "U3") (pin "3") (pinfunction "CE_3") (pintype "passive"))
    )
    (net (code "49") (name "VCC_24V") (class "Default")
      (node (ref "C79") (pin "2") (pinfunction "2_2") (pintype "passive"))
      (node (ref "C80") (pin "1") (pinfunction "1_1") (pintype "passive"))
      (node (ref "L2") (pin "2") (pinfunction "2_2") (pintype "passive"))
      (node (ref "R90") (pin "1") (pinfunction "1_1") (pintype "passive"))
    )
    (net (code "50") (name "VCC_36V") (class "Default")
      (node (ref "C71") (pin "1") (pinfunction "1_1") (pintype "passive"))
      (node (ref "C73") (pin "2") (pinfunction "2_2") (pintype "passive"))
      (node (ref "C76") (pin "1") (pinfunction "1_1") (pintype "passive"))
      (node (ref "C78") (pin "2") (pinfunction "2_2") (pintype "passive"))
      (node (ref "R88") (pin "2") (pinfunction "2_2") (pintype "passive"))
      (node (ref "R91") (pin "2") (pinfunction "2_2") (pintype "passive"))
      (node (ref "T13") (pin "2") (pinfunction "2_2") (pintype "passive"))
      (node (ref "T2") (pin "2") (pinfunction "2_2") (pintype "passive"))
      (node (ref "T4") (pin "1") (pintype "passive"))
      (node (ref "U26") (pin "7") (pinfunction "VIN_7") (pintype "passive"))
      (node (ref "U27") (pin "7") (pinfunction "VIN_7") (pintype "passive"))
    )
    (net (code "51") (name "unconnected-(U3-NC-Pad4)") (class "Default")
      (node (ref "U3") (pin "4") (pinfunction "NC_4") (pintype "passive"))
    )
    (net (code "52") (name "unconnected-(U26-NC-Pad2)") (class "Default")
      (node (ref "U26") (pin "2") (pinfunction "NC_2") (pintype "passive+no_connect"))
    )
    (net (code "53") (name "unconnected-(U26-NC-Pad3)") (class "Default")
      (node (ref "U26") (pin "3") (pinfunction "NC_3") (pintype "passive+no_connect"))
    )
    (net (code "54") (name "unconnected-(U27-NC-Pad2)") (class "Default")
      (node (ref "U27") (pin "2") (pinfunction "NC_2") (pintype "passive+no_connect"))
    )
    (net (code "55") (name "unconnected-(U27-NC-Pad3)") (class "Default")
      (node (ref "U27") (pin "3") (pinfunction "NC_3") (pintype "passive+no_connect"))
    )
  )
)
